# FE.net
KiCad netlist of a schematic drawn in Altium Designer
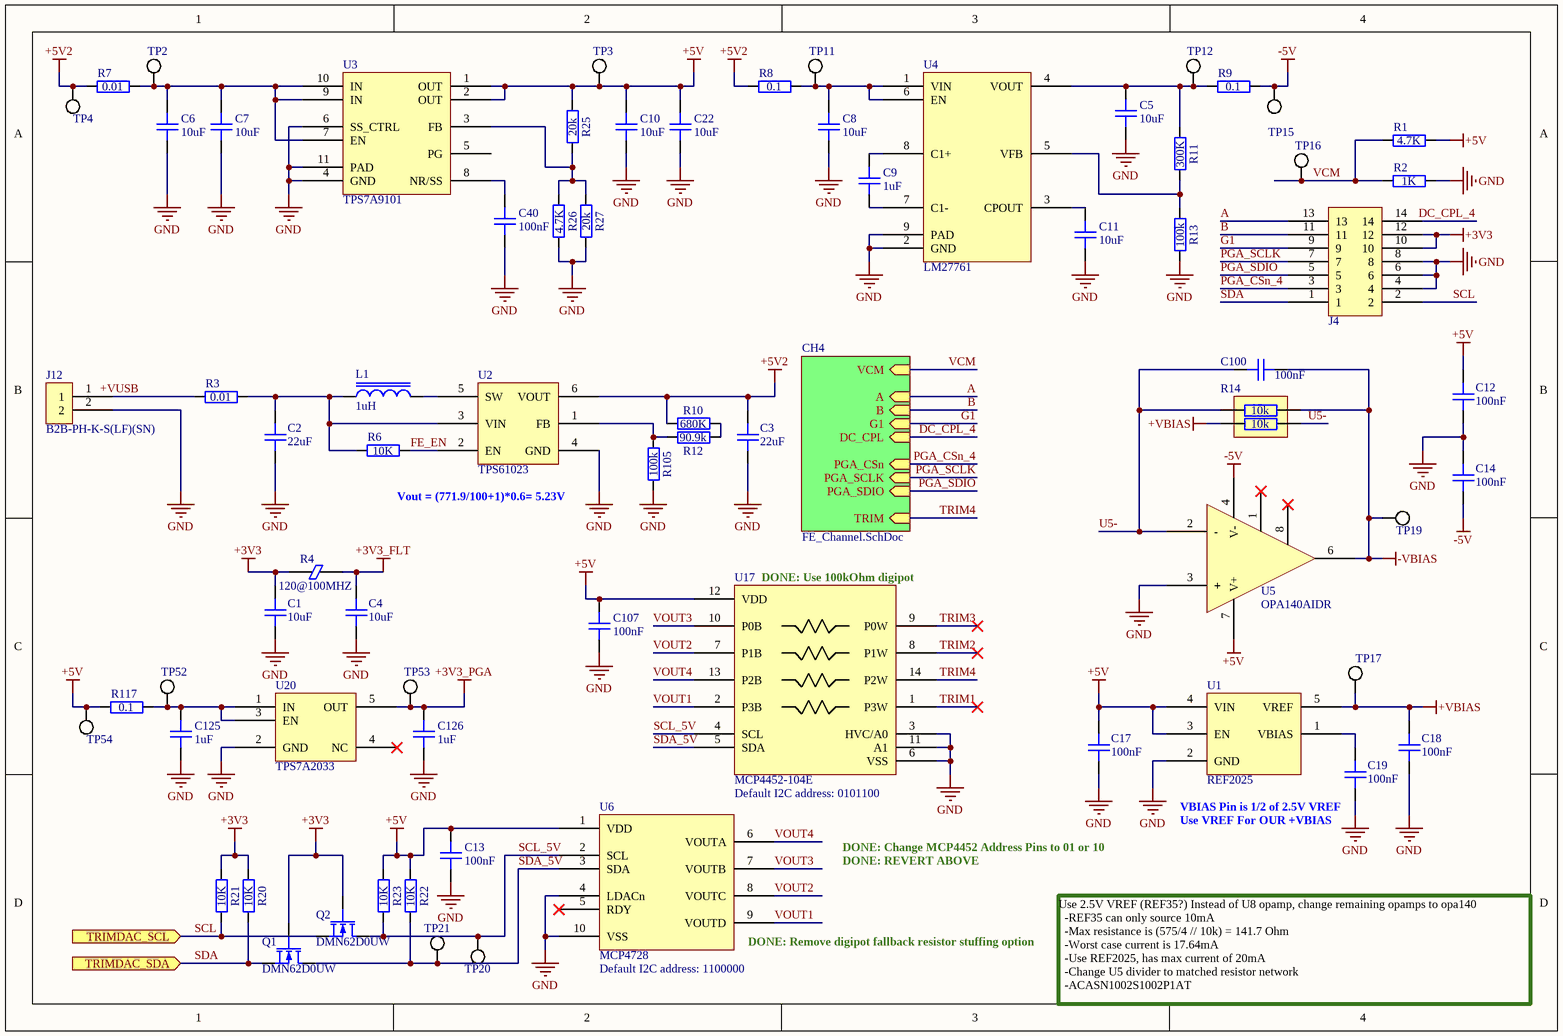
[diagram p0: FE.SchDoc]

(export (version "E")
  (design (tool "Eeschema 10.0.6"))
  (components
    (comp (ref "C1")
      (value "10uF")
      (footprint "GEN_C_0603")
      (fields
        (field (name "MANUFACTURER") "Murata")
        (field (name "HOUSE PART NUMBER") "C-10uF-0603-002")
        (field (name "MANUFACTURER PART NUMBER") "GRM188R61A106ME69D")
      )
      (libsource (lib "DSO") (part "CAP 10uF 10V X5R 0603"))
    )
    (comp (ref "C2")
      (value "22uF")
      (footprint "GEN_C_0805")
      (fields
        (field (name "HOUSE PART NUMBER") "C-22uF-0805-002")
        (field (name "MANUFACTURER") "Murata")
        (field (name "MANUFACTURER PART NUMBER") "GRM21BR61E226ME44L")
      )
      (libsource (lib "DSO") (part "CAP 22uF 25V X5R 0805"))
    )
    (comp (ref "C3")
      (value "22uF")
      (footprint "GEN_C_0805")
      (fields
        (field (name "HOUSE PART NUMBER") "C-22uF-0805-002")
        (field (name "MANUFACTURER") "Murata")
        (field (name "MANUFACTURER PART NUMBER") "GRM21BR61E226ME44L")
      )
      (libsource (lib "DSO") (part "CAP 22uF 25V X5R 0805"))
    )
    (comp (ref "C4")
      (value "10uF")
      (footprint "GEN_C_0603")
      (fields
        (field (name "MANUFACTURER") "Murata")
        (field (name "HOUSE PART NUMBER") "C-10uF-0603-002")
        (field (name "MANUFACTURER PART NUMBER") "GRM188R61A106ME69D")
      )
      (libsource (lib "DSO") (part "CAP 10uF 10V X5R 0603"))
    )
    (comp (ref "C5")
      (value "10uF")
      (footprint "GEN_C_0603")
      (fields
        (field (name "HOUSE PART NUMBER") "C-10uF-0603-002")
        (field (name "MANUFACTURER") "Murata")
        (field (name "MANUFACTURER PART NUMBER") "GRM188R61A106ME69D")
      )
      (libsource (lib "DSO") (part "CAP 10uF 10V X5R 0603"))
    )
    (comp (ref "C6")
      (value "10uF")
      (footprint "GEN_C_0603")
      (fields
        (field (name "HOUSE PART NUMBER") "C-10uF-0603-002")
        (field (name "MANUFACTURER") "Murata")
        (field (name "MANUFACTURER PART NUMBER") "GRM188R61A106ME69D")
      )
      (libsource (lib "DSO") (part "CAP 10uF 10V X5R 0603"))
    )
    (comp (ref "C7")
      (value "10uF")
      (footprint "GEN_C_0603")
      (fields
        (field (name "HOUSE PART NUMBER") "C-10uF-0603-002")
        (field (name "MANUFACTURER") "Murata")
        (field (name "MANUFACTURER PART NUMBER") "GRM188R61A106ME69D")
      )
      (libsource (lib "DSO") (part "CAP 10uF 10V X5R 0603"))
    )
    (comp (ref "C8")
      (value "10uF")
      (footprint "GEN_C_0603")
      (fields
        (field (name "HOUSE PART NUMBER") "C-10uF-0603-002")
        (field (name "MANUFACTURER") "Murata")
        (field (name "MANUFACTURER PART NUMBER") "GRM188R61A106ME69D")
      )
      (libsource (lib "DSO") (part "CAP 10uF 10V X5R 0603"))
    )
    (comp (ref "C9")
      (value "1uF")
      (footprint "GEN_C_0402")
      (fields
        (field (name "MANUFACTURER") "Murata")
        (field (name "MANUFACTURER PART NUMBER") "GRM155R61E105KA12D")
      )
      (libsource (lib "DSO") (part "CAP 1uF 25V X5R 0402"))
    )
    (comp (ref "C10")
      (value "10uF")
      (footprint "GEN_C_0603")
      (fields
        (field (name "HOUSE PART NUMBER") "C-10uF-0603-002")
        (field (name "MANUFACTURER") "Murata")
        (field (name "MANUFACTURER PART NUMBER") "GRM188R61A106ME69D")
      )
      (libsource (lib "DSO") (part "CAP 10uF 10V X5R 0603"))
    )
    (comp (ref "C11")
      (value "10uF")
      (footprint "GEN_C_0603")
      (fields
        (field (name "HOUSE PART NUMBER") "C-10uF-0603-002")
        (field (name "MANUFACTURER") "Murata")
        (field (name "MANUFACTURER PART NUMBER") "GRM188R61A106ME69D")
      )
      (libsource (lib "DSO") (part "CAP 10uF 10V X5R 0603"))
    )
    (comp (ref "C12")
      (value "100nF")
      (footprint "GEN_C_0402")
      (fields
        (field (name "HOUSE PART NUMBER") "C-100nF-0402-002")
        (field (name "MANUFACTURER") "Murata")
        (field (name "MANUFACTURER PART NUMBER") "GCM155R71C104KA55D")
      )
      (libsource (lib "DSO") (part "CAP 100nF 16V X7R 0402"))
    )
    (comp (ref "C13")
      (value "100nF")
      (footprint "GEN_C_0402")
      (fields
        (field (name "HOUSE PART NUMBER") "C-100nF-0402-002")
        (field (name "MANUFACTURER") "Murata")
        (field (name "MANUFACTURER PART NUMBER") "GCM155R71C104KA55D")
      )
      (libsource (lib "DSO") (part "CAP 100nF 16V X7R 0402"))
    )
    (comp (ref "C14")
      (value "100nF")
      (footprint "GEN_C_0402")
      (fields
        (field (name "HOUSE PART NUMBER") "C-100nF-0402-002")
        (field (name "MANUFACTURER") "Murata")
        (field (name "MANUFACTURER PART NUMBER") "GCM155R71C104KA55D")
      )
      (libsource (lib "DSO") (part "CAP 100nF 16V X7R 0402"))
    )
    (comp (ref "C17")
      (value "100nF")
      (footprint "GEN_C_0402")
      (fields
        (field (name "HOUSE PART NUMBER") "C-100nF-0402-002")
        (field (name "MANUFACTURER") "Murata")
        (field (name "MANUFACTURER PART NUMBER") "GCM155R71C104KA55D")
      )
      (libsource (lib "DSO") (part "CAP 100nF 16V X7R 0402"))
    )
    (comp (ref "C18")
      (value "100nF")
      (footprint "GEN_C_0402")
      (fields
        (field (name "HOUSE PART NUMBER") "C-100nF-0402-002")
        (field (name "MANUFACTURER") "Murata")
        (field (name "MANUFACTURER PART NUMBER") "GCM155R71C104KA55D")
      )
      (libsource (lib "DSO") (part "CAP 100nF 16V X7R 0402"))
    )
    (comp (ref "C19")
      (value "100nF")
      (footprint "GEN_C_0402")
      (fields
        (field (name "HOUSE PART NUMBER") "C-100nF-0402-002")
        (field (name "MANUFACTURER") "Murata")
        (field (name "MANUFACTURER PART NUMBER") "GCM155R71C104KA55D")
      )
      (libsource (lib "DSO") (part "CAP 100nF 16V X7R 0402"))
    )
    (comp (ref "C22")
      (value "10uF")
      (footprint "GEN_C_0603")
      (fields
        (field (name "HOUSE PART NUMBER") "C-10uF-0603-002")
        (field (name "MANUFACTURER") "Murata")
        (field (name "MANUFACTURER PART NUMBER") "GRM188R61A106ME69D")
      )
      (libsource (lib "DSO") (part "CAP 10uF 10V X5R 0603"))
    )
    (comp (ref "C40")
      (value "100nF")
      (footprint "GEN_C_0402")
      (fields
        (field (name "MANUFACTURER") "Murata")
        (field (name "HOUSE PART NUMBER") "C-100nF-0402-002")
        (field (name "MANUFACTURER PART NUMBER") "GCM155R71C104KA55D")
      )
      (libsource (lib "DSO") (part "CAP 100nF 16V X7R 0402"))
    )
    (comp (ref "C100")
      (value "100nF")
      (footprint "GEN_C_0402")
      (fields
        (field (name "HOUSE PART NUMBER") "C-100nF-0402-002")
        (field (name "MANUFACTURER") "Murata")
        (field (name "MANUFACTURER PART NUMBER") "GCM155R71C104KA55D")
      )
      (libsource (lib "DSO") (part "CAP 100nF 16V X7R 0402"))
    )
    (comp (ref "C107")
      (value "100nF")
      (footprint "GEN_C_0402")
      (fields
        (field (name "HOUSE PART NUMBER") "C-100nF-0402-002")
        (field (name "MANUFACTURER") "Murata")
        (field (name "MANUFACTURER PART NUMBER") "GCM155R71C104KA55D")
      )
      (libsource (lib "DSO") (part "CAP 100nF 16V X7R 0402"))
    )
    (comp (ref "C125")
      (value "1uF")
      (footprint "GEN_C_0402")
      (fields
        (field (name "MANUFACTURER") "Murata")
        (field (name "MANUFACTURER PART NUMBER") "GRM155R61E105KA12D")
      )
      (libsource (lib "DSO") (part "CAP 1uF 25V X5R 0402"))
    )
    (comp (ref "C126")
      (value "1uF")
      (footprint "GEN_C_0402")
      (fields
        (field (name "MANUFACTURER") "Murata")
        (field (name "MANUFACTURER PART NUMBER") "GRM155R61E105KA12D")
      )
      (libsource (lib "DSO") (part "CAP 1uF 25V X5R 0402"))
    )
    (comp (ref "J4")
      (value "2.54mm 2X7 Pin TH")
      (footprint "GEN_2.54mm_2X7_Pin_TH_RA")
      (libsource (lib "DSO") (part "CONN 2.54mm 2X7 Pin TH RA"))
    )
    (comp (ref "J12")
      (value "B2B-PH-K-S(LF)(SN)")
      (footprint "JST_B2B-PH-K-S(LF)(SN)")
      (fields
        (field (name "MANUFACTURER") "JST")
        (field (name "MANUFACTURER PART NUMBER") "B2B-PH-K-S-LF-SN")
      )
      (libsource (lib "DSO") (part "CONN JST PH 2 Pin TH"))
    )
    (comp (ref "L1")
      (value "1uH")
      (footprint "GEN_L_1210")
      (fields
        (field (name "MANUFACTURER") "Murata")
        (field (name "MANUFACTURER PART NUMBER") "1277AS-H-1R0M=P2")
      )
      (libsource (lib "DSO") (part "IND 1uH 3.1A 45 MOHM 1210"))
    )
    (comp (ref "Q1")
      (value "DMN62D0UW")
      (footprint "GEN_SOT_323")
      (fields (field (name "HOUSE PART NUMBER") "DMN62D0UW-7") (field (name "MANUFACTURER") "Diodes"))
      (libsource (lib "DSO") (part "NMOS DMN62D0UW"))
    )
    (comp (ref "Q2")
      (value "DMN62D0UW")
      (footprint "GEN_SOT_323")
      (fields (field (name "HOUSE PART NUMBER") "DMN62D0UW-7") (field (name "MANUFACTURER") "Diodes"))
      (libsource (lib "DSO") (part "NMOS DMN62D0UW"))
    )
    (comp (ref "R1")
      (value "4.7K")
      (footprint "GEN_R_0402")
      (fields
        (field (name "TOLERANCE") "1%")
        (field (name "MANUFACTURER") "Panasonic")
        (field (name "MANUFACTURER PART NUMBER") "ERJ-2RKF4701X")
      )
      (libsource (lib "DSO") (part "RES 4.7K OHM 1% 1/10W 0402"))
    )
    (comp (ref "R2")
      (value "1K")
      (footprint "GEN_R_0402")
      (fields
        (field (name "TOLERANCE") "1%")
        (field (name "MANUFACTURER") "Yageo")
        (field (name "HOUSE PART NUMBER") "R-1K-0402-1%-001")
      )
      (libsource (lib "DSO") (part "RES 1K OHM 1% 1/10W 0402"))
    )
    (comp (ref "R3")
      (value "0.01")
      (footprint "GEN_R_0603")
      (fields
        (field (name "TOLERANCE") "1%")
        (field (name "HOUSE PART NUMBER") "R-0.01-0603-1%-001")
        (field (name "MANUFACTURER") "Susumu")
      )
      (libsource (lib "") (part "RES 0.01 OHM 1% 1/4W 0603_1"))
    )
    (comp (ref "R4")
      (value "120@100MHZ")
      (footprint "GEN_R_0402")
      (fields (field (name "MANUFACTURER") "Murata") (field (name "HOUSE PART NUMBER") "BLM15PX121SN1D"))
      (libsource (lib "DSO") (part "FERRITE BEAD 120 OHM 0402"))
    )
    (comp (ref "R6")
      (value "10K")
      (footprint "GEN_R_0402")
      (fields
        (field (name "TOLERANCE") "1%")
        (field (name "MANUFACTURER") "Panasonic")
        (field (name "MANUFACTURER PART NUMBER") "ERJ-2RKF1002X")
      )
      (libsource (lib "DSO") (part "RES 10K OHM 1% 1/10W 0402"))
    )
    (comp (ref "R7")
      (value "0.01")
      (footprint "GEN_R_0603")
      (fields
        (field (name "TOLERANCE") "1%")
        (field (name "HOUSE PART NUMBER") "R-0.01-0603-1%-001")
        (field (name "MANUFACTURER") "Susumu")
      )
      (libsource (lib "DSO") (part "RES 0.01 OHM 1% 1/4W 0603"))
    )
    (comp (ref "R8")
      (value "0.1")
      (footprint "GEN_R_0402")
      (fields
        (field (name "TOLERANCE") "1%")
        (field (name "MANUFACTURER") "Panasonic")
        (field (name "MANUFACTURER PART NUMBER") "ERJ-2BSFR10X")
      )
      (libsource (lib "DSO") (part "RES 0.1 OHM 1% 1/6W 0402"))
    )
    (comp (ref "R9")
      (value "0.1")
      (footprint "GEN_R_0402")
      (fields
        (field (name "TOLERANCE") "1%")
        (field (name "MANUFACTURER") "Panasonic")
        (field (name "MANUFACTURER PART NUMBER") "ERJ-2BSFR10X")
      )
      (libsource (lib "DSO") (part "RES 0.1 OHM 1% 1/6W 0402"))
    )
    (comp (ref "R10")
      (value "680K")
      (footprint "GEN_R_0402")
      (fields
        (field (name "TOLERANCE") "1%")
        (field (name "MANUFACTURER") "Yageo")
        (field (name "MANUFACTURER PART NUMBER") "RC0402FR-07681KL")
      )
      (libsource (lib "DSO") (part "RES 680K OHM 1% 1/16W 0402"))
    )
    (comp (ref "R11")
      (value "300K")
      (footprint "GEN_R_0402")
      (fields
        (field (name "TOLERANCE") "1%")
        (field (name "MANUFACTURER") "Panasonic")
        (field (name "MANUFACTURER PART NUMBER") "ERJ-2RKF3003X")
      )
      (libsource (lib "DSO") (part "RES 300K OHM 1% 1/10W 0402"))
    )
    (comp (ref "R12")
      (value "90.9k")
      (footprint "GEN_R_0402")
      (fields
        (field (name "TOLERANCE") "1%")
        (field (name "MANUFACTURER") "Yageo")
        (field (name "MANUFACTURER PART NUMBER") "RC0402FR-0790K9L")
      )
      (libsource (lib "DSO") (part "RES 90.9K OHM 1% 1/16W 0402"))
    )
    (comp (ref "R13")
      (value "100k")
      (footprint "GEN_R_0402")
      (fields
        (field (name "TOLERANCE") "1%")
        (field (name "HOUSE PART NUMBER") "R-100K-0402-1%-001")
        (field (name "MANUFACTURER") "Yageo")
      )
      (libsource (lib "DSO") (part "RES 100K OHM 1% 1/10W 0402"))
    )
    (comp (ref "R14")
      (value "10K")
      (footprint "GEN_R_2ARRAY_0606")
      (fields
        (field (name "TOLERANCE") "1%")
        (field (name "MANUFACTURER") "Vishay Beyschlag")
        (field (name "MANUFACTURER PART NUMBER") "ACASN1002S1002P1ATF1002X")
      )
      (libsource (lib "DSO") (part "RES ARRAY 2x 10K OHM 0.05% 0606"))
    )
    (comp (ref "R20")
      (value "10K")
      (footprint "GEN_R_0402")
      (fields
        (field (name "TOLERANCE") "1%")
        (field (name "MANUFACTURER") "Panasonic")
        (field (name "MANUFACTURER PART NUMBER") "ERJ-2RKF1002X")
      )
      (libsource (lib "") (part "RES 10K OHM 1% 1/10W 0402_1"))
    )
    (comp (ref "R21")
      (value "10K")
      (footprint "GEN_R_0402")
      (fields
        (field (name "TOLERANCE") "1%")
        (field (name "MANUFACTURER") "Panasonic")
        (field (name "MANUFACTURER PART NUMBER") "ERJ-2RKF1002X")
      )
      (libsource (lib "") (part "RES 10K OHM 1% 1/10W 0402_1"))
    )
    (comp (ref "R22")
      (value "10K")
      (footprint "GEN_R_0402")
      (fields
        (field (name "TOLERANCE") "1%")
        (field (name "MANUFACTURER") "Panasonic")
        (field (name "MANUFACTURER PART NUMBER") "ERJ-2RKF1002X")
      )
      (libsource (lib "") (part "RES 10K OHM 1% 1/10W 0402_1"))
    )
    (comp (ref "R23")
      (value "10K")
      (footprint "GEN_R_0402")
      (fields
        (field (name "TOLERANCE") "1%")
        (field (name "MANUFACTURER") "Panasonic")
        (field (name "MANUFACTURER PART NUMBER") "ERJ-2RKF1002X")
      )
      (libsource (lib "") (part "RES 10K OHM 1% 1/10W 0402_1"))
    )
    (comp (ref "R25")
      (value "20k")
      (footprint "GEN_R_0402")
      (fields
        (field (name "TOLERANCE") "1%")
        (field (name "MANUFACTURER") "Yageo")
        (field (name "MANUFACTURER PART NUMBER") "RC0402FR-0720KL")
      )
      (libsource (lib "DSO") (part "RES 20K OHM 1% 1/16W 0402"))
    )
    (comp (ref "R26")
      (value "4.7K")
      (footprint "GEN_R_0402")
      (fields
        (field (name "TOLERANCE") "1%")
        (field (name "MANUFACTURER") "Panasonic")
        (field (name "MANUFACTURER PART NUMBER") "ERJ-2RKF4701X")
      )
      (libsource (lib "DSO") (part "RES 4.7K OHM 1% 1/10W 0402"))
    )
    (comp (ref "R27")
      (value "20k")
      (footprint "GEN_R_0402")
      (fields
        (field (name "TOLERANCE") "1%")
        (field (name "MANUFACTURER") "Yageo")
        (field (name "MANUFACTURER PART NUMBER") "RC0402FR-0720KL")
      )
      (libsource (lib "DSO") (part "RES 20K OHM 1% 1/16W 0402"))
    )
    (comp (ref "R105")
      (value "100k")
      (footprint "GEN_R_0402")
      (fields
        (field (name "TOLERANCE") "1%")
        (field (name "HOUSE PART NUMBER") "R-100K-0402-1%-001")
        (field (name "MANUFACTURER") "Yageo")
      )
      (libsource (lib "DSO") (part "RES 100K OHM 1% 1/10W 0402"))
    )
    (comp (ref "R117")
      (value "0.1")
      (footprint "GEN_R_0402")
      (fields
        (field (name "TOLERANCE") "1%")
        (field (name "MANUFACTURER") "Panasonic")
        (field (name "MANUFACTURER PART NUMBER") "ERJ-2BSFR10X")
      )
      (libsource (lib "DSO") (part "RES 0.1 OHM 1% 1/6W 0402"))
    )
    (comp (ref "TP2") (value "PCB") (footprint "GEN_TP_PCB") (libsource (lib "DSO") (part "TP PCB 1mm")))
    (comp (ref "TP3") (value "PCB") (footprint "GEN_TP_PCB") (libsource (lib "DSO") (part "TP PCB 1mm")))
    (comp (ref "TP4") (value "PCB") (footprint "GEN_TP_PCB") (libsource (lib "DSO") (part "TP PCB 1mm")))
    (comp (ref "TP11") (value "PCB") (footprint "GEN_TP_PCB") (libsource (lib "DSO") (part "TP PCB 1mm")))
    (comp (ref "TP12") (value "PCB") (footprint "GEN_TP_PCB") (libsource (lib "DSO") (part "TP PCB 1mm")))
    (comp (ref "TP15") (value "PCB") (footprint "GEN_TP_PCB") (libsource (lib "DSO") (part "TP PCB 1mm")))
    (comp (ref "TP16") (value "PCB") (footprint "GEN_TP_PCB") (libsource (lib "DSO") (part "TP PCB 1mm")))
    (comp (ref "TP17") (value "PCB") (footprint "GEN_TP_PCB") (libsource (lib "DSO") (part "TP PCB 1mm")))
    (comp (ref "TP19") (value "PCB") (footprint "GEN_TP_PCB") (libsource (lib "DSO") (part "TP PCB 1mm")))
    (comp (ref "TP20") (value "PCB") (footprint "GEN_TP_PCB") (libsource (lib "DSO") (part "TP PCB 1mm")))
    (comp (ref "TP21") (value "PCB") (footprint "GEN_TP_PCB") (libsource (lib "DSO") (part "TP PCB 1mm")))
    (comp (ref "TP52") (value "PCB") (footprint "GEN_TP_PCB") (libsource (lib "DSO") (part "TP PCB 1mm")))
    (comp (ref "TP53") (value "PCB") (footprint "GEN_TP_PCB") (libsource (lib "DSO") (part "TP PCB 1mm")))
    (comp (ref "TP54") (value "PCB") (footprint "GEN_TP_PCB") (libsource (lib "DSO") (part "TP PCB 1mm")))
    (comp (ref "U1")
      (value "REF2025")
      (footprint "GEN_SOT23_5_950_2900X1600X1450")
      (libsource (lib "DSO") (part "IC VREF REF2025"))
    )
    (comp (ref "U2")
      (value "TPS61023")
      (footprint "TI_SOT563_DRL0006A")
      (fields
        (field (name "MANUFACTURER") "Texas Instruments")
        (field (name "MANUFACTURER PART NUMBER") "TPS61023DRLT")
      )
      (libsource (lib "DSO") (part "IC BOOST TPS61023"))
    )
    (comp (ref "U3")
      (value "TPS7A9101")
      (footprint "TI_WSON10_DSK0010A")
      (libsource (lib "DSO") (part "IC LDO TPS7A9101"))
    )
    (comp (ref "U4")
      (value "LM27761")
      (footprint "TI_WSON8_DSG0008A")
      (fields
        (field (name "MANUFACTURER") "Texas Instruments")
        (field (name "MANUFACTURER PART NUMBER") "LM27761DSGR")
      )
      (libsource (lib "DSO") (part "IC CPUMP LM27761"))
    )
    (comp (ref "U5")
      (value "OPA140AIDR")
      (footprint "TI_SOIC8_D0008A")
      (fields (field (name "MANUFACTURER") "Texas Instruments"))
      (libsource (lib "DSO") (part "IC OPAMP OPA140"))
    )
    (comp (ref "U6")
      (value "MCP4728")
      (footprint "MC_MSOP10_UN")
      (fields (field (name "MANUFACTURER") "Microchip"))
      (libsource (lib "DSO") (part "IC DAC QUAD MCP4728"))
    )
    (comp (ref "U17")
      (value "MCP4452-104E")
      (footprint "MC_TSSOP14")
      (fields (field (name "MANUFACTURER") "Microchip"))
      (libsource (lib "DSO") (part "IC DIGIPOT QUAD MCP4452-104E"))
    )
    (comp (ref "U20")
      (value "TPS7A2033")
      (footprint "GEN_SOT23_5_950_2900X1600X1450")
      (fields
        (field (name "MANUFACTURER") "Texas Instruments")
        (field (name "MANUFACTURER PART NUMBER") "TPS7A2033PDBVR")
      )
      (libsource (lib "DSO") (part "IC LDO TPS7A2033"))
    )
  )
  (nets
    (net (code "1") (name "+3V3") (class "Default")
      (node (ref "C1") (pin "2") (pinfunction "2_2") (pintype "passive"))
      (node (ref "J4") (pin "10") (pinfunction "10_10") (pintype "passive"))
      (node (ref "J4") (pin "12") (pinfunction "12_12") (pintype "passive"))
      (node (ref "Q1") (pin "2") (pinfunction "G_2") (pintype "passive"))
      (node (ref "Q2") (pin "2") (pinfunction "G_2") (pintype "passive"))
      (node (ref "R20") (pin "2") (pinfunction "2_2") (pintype "passive"))
      (node (ref "R21") (pin "2") (pinfunction "2_2") (pintype "passive"))
      (node (ref "R4") (pin "1") (pinfunction "1_1") (pintype "passive"))
    )
    (net (code "2") (name "+3V3_FLT") (class "Default")
      (node (ref "C4") (pin "2") (pinfunction "2_2") (pintype "passive"))
      (node (ref "R4") (pin "2") (pinfunction "2_2") (pintype "passive"))
    )
    (net (code "3") (name "+3V3_PGA") (class "Default")
      (node (ref "C126") (pin "2") (pinfunction "2_2") (pintype "passive"))
      (node (ref "TP53") (pin "1") (pinfunction "1_1") (pintype "passive"))
      (node (ref "U20") (pin "5") (pinfunction "OUT_5") (pintype "power_in"))
    )
    (net (code "4") (name "+5V") (class "Default")
      (node (ref "C10") (pin "2") (pinfunction "2_2") (pintype "passive"))
      (node (ref "C107") (pin "2") (pinfunction "2_2") (pintype "passive"))
      (node (ref "C12") (pin "1") (pinfunction "1_1") (pintype "passive"))
      (node (ref "C13") (pin "2") (pinfunction "2_2") (pintype "passive"))
      (node (ref "C17") (pin "1") (pinfunction "1_1") (pintype "passive"))
      (node (ref "C22") (pin "2") (pinfunction "2_2") (pintype "passive"))
      (node (ref "R1") (pin "2") (pinfunction "2_2") (pintype "passive"))
      (node (ref "R117") (pin "1") (pinfunction "1_1") (pintype "passive"))
      (node (ref "R22") (pin "2") (pinfunction "2_2") (pintype "passive"))
      (node (ref "R23") (pin "2") (pinfunction "2_2") (pintype "passive"))
      (node (ref "R25") (pin "2") (pinfunction "2_2") (pintype "passive"))
      (node (ref "TP3") (pin "1") (pinfunction "1_1") (pintype "passive"))
      (node (ref "TP54") (pin "1") (pinfunction "1_1") (pintype "passive"))
      (node (ref "U1") (pin "3") (pinfunction "EN_3") (pintype "passive"))
      (node (ref "U1") (pin "4") (pinfunction "VIN_4") (pintype "passive"))
      (node (ref "U17") (pin "12") (pinfunction "VDD_12") (pintype "power_in"))
      (node (ref "U3") (pin "1") (pinfunction "OUT_1") (pintype "power_in"))
      (node (ref "U3") (pin "2") (pinfunction "OUT_2") (pintype "power_in"))
      (node (ref "U5") (pin "7") (pinfunction "V+_7") (pintype "passive"))
      (node (ref "U6") (pin "1") (pinfunction "VDD_1") (pintype "power_in"))
    )
    (net (code "5") (name "+5V2") (class "Default")
      (node (ref "C3") (pin "2") (pinfunction "2_2") (pintype "passive"))
      (node (ref "R10") (pin "2") (pinfunction "2_2") (pintype "passive"))
      (node (ref "R7") (pin "1") (pinfunction "1_1") (pintype "passive"))
      (node (ref "R8") (pin "1") (pinfunction "1_1") (pintype "passive"))
      (node (ref "TP4") (pin "1") (pinfunction "1_1") (pintype "passive"))
      (node (ref "U2") (pin "6") (pinfunction "VOUT_6") (pintype "passive"))
    )
    (net (code "6") (name "+VBIAS") (class "Default")
      (node (ref "C18") (pin "1") (pinfunction "1_1") (pintype "passive"))
      (node (ref "R14") (pin "2") (pinfunction "2_2") (pintype "passive"))
      (node (ref "TP17") (pin "1") (pinfunction "1_1") (pintype "passive"))
      (node (ref "U1") (pin "5") (pinfunction "VREF_5") (pintype "passive"))
    )
    (net (code "7") (name "-5V") (class "Default")
      (node (ref "C14") (pin "2") (pinfunction "2_2") (pintype "passive"))
      (node (ref "R9") (pin "2") (pinfunction "2_2") (pintype "passive"))
      (node (ref "TP15") (pin "1") (pinfunction "1_1") (pintype "passive"))
      (node (ref "U5") (pin "4") (pinfunction "V-_4") (pintype "passive"))
    )
    (net (code "8") (name "-VBIAS") (class "Default")
      (node (ref "C100") (pin "1") (pinfunction "1_1") (pintype "passive"))
      (node (ref "R14") (pin "4") (pinfunction "4_4") (pintype "passive"))
      (node (ref "TP19") (pin "1") (pinfunction "1_1") (pintype "passive"))
      (node (ref "U5") (pin "6") (pinfunction "OUT_6") (pintype "passive"))
    )
    (net (code "9") (name "/+VUSB") (class "Default")
      (node (ref "J12") (pin "1") (pinfunction "1_1") (pintype "passive"))
      (node (ref "R3") (pin "2") (pinfunction "2_2") (pintype "passive"))
    )
    (net (code "10") (name "/A") (class "Default")
      (node (ref "J4") (pin "13") (pinfunction "13_13") (pintype "passive"))
    )
    (net (code "11") (name "/B") (class "Default")
      (node (ref "J4") (pin "11") (pinfunction "11_11") (pintype "passive"))
    )
    (net (code "12") (name "/DC_CPL_4") (class "Default")
      (node (ref "J4") (pin "14") (pinfunction "14_14") (pintype "passive"))
    )
    (net (code "13") (name "/FE_EN") (class "Default")
      (node (ref "R6") (pin "1") (pinfunction "1_1") (pintype "passive"))
      (node (ref "U2") (pin "2") (pinfunction "EN_2") (pintype "passive"))
    )
    (net (code "14") (name "/G1") (class "Default")
      (node (ref "J4") (pin "9") (pinfunction "9_9") (pintype "passive"))
    )
    (net (code "15") (name "/PGA_CSn_4") (class "Default")
      (node (ref "J4") (pin "3") (pinfunction "3_3") (pintype "passive"))
    )
    (net (code "16") (name "/PGA_SCLK") (class "Default")
      (node (ref "J4") (pin "7") (pinfunction "7_7") (pintype "passive"))
    )
    (net (code "17") (name "/PGA_SDIO") (class "Default")
      (node (ref "J4") (pin "5") (pinfunction "5_5") (pintype "passive"))
    )
    (net (code "18") (name "/SCL") (class "Default")
      (node (ref "J4") (pin "2") (pinfunction "2_2") (pintype "passive"))
      (node (ref "Q2") (pin "3") (pinfunction "S_3") (pintype "passive"))
      (node (ref "R21") (pin "1") (pinfunction "1_1") (pintype "passive"))
    )
    (net (code "19") (name "/SCL_5V") (class "Default")
      (node (ref "Q2") (pin "1") (pinfunction "D_1") (pintype "passive"))
      (node (ref "R23") (pin "1") (pinfunction "1_1") (pintype "passive"))
      (node (ref "TP20") (pin "1") (pinfunction "1_1") (pintype "passive"))
      (node (ref "U17") (pin "4") (pinfunction "SCL_4") (pintype "passive"))
      (node (ref "U6") (pin "2") (pinfunction "SCL_2") (pintype "passive"))
    )
    (net (code "20") (name "/SDA") (class "Default")
      (node (ref "J4") (pin "1") (pinfunction "1_1") (pintype "passive"))
      (node (ref "Q1") (pin "3") (pinfunction "S_3") (pintype "passive"))
      (node (ref "R20") (pin "1") (pinfunction "1_1") (pintype "passive"))
    )
    (net (code "21") (name "/SDA_5V") (class "Default")
      (node (ref "Q1") (pin "1") (pinfunction "D_1") (pintype "passive"))
      (node (ref "R22") (pin "1") (pinfunction "1_1") (pintype "passive"))
      (node (ref "TP21") (pin "1") (pinfunction "1_1") (pintype "passive"))
      (node (ref "U17") (pin "5") (pinfunction "SDA_5") (pintype "passive"))
      (node (ref "U6") (pin "3") (pinfunction "SDA_3") (pintype "passive"))
    )
    (net (code "22") (name "/TRIM1") (class "Default")
      (node (ref "U17") (pin "1") (pinfunction "P3W_1") (pintype "passive+no_connect"))
    )
    (net (code "23") (name "/TRIM2") (class "Default")
      (node (ref "U17") (pin "8") (pinfunction "P1W_8") (pintype "passive+no_connect"))
    )
    (net (code "24") (name "/TRIM3") (class "Default")
      (node (ref "U17") (pin "9") (pinfunction "P0W_9") (pintype "passive+no_connect"))
    )
    (net (code "25") (name "/TRIM4") (class "Default")
      (node (ref "U17") (pin "14") (pinfunction "P2W_14") (pintype "passive"))
    )
    (net (code "26") (name "/U5-") (class "Default")
      (node (ref "C100") (pin "2") (pinfunction "2_2") (pintype "passive"))
      (node (ref "R14") (pin "1") (pinfunction "1_1") (pintype "passive"))
      (node (ref "R14") (pin "3") (pinfunction "3_3") (pintype "passive"))
      (node (ref "U5") (pin "2") (pinfunction "-_2") (pintype "passive"))
    )
    (net (code "27") (name "/VCM") (class "Default")
      (node (ref "R1") (pin "1") (pinfunction "1_1") (pintype "passive"))
      (node (ref "R2") (pin "1") (pinfunction "1_1") (pintype "passive"))
      (node (ref "TP16") (pin "1") (pinfunction "1_1") (pintype "passive"))
    )
    (net (code "28") (name "/VOUT1") (class "Default")
      (node (ref "U17") (pin "2") (pinfunction "P3B_2") (pintype "passive"))
      (node (ref "U6") (pin "9") (pinfunction "VOUTD_9") (pintype "passive"))
    )
    (net (code "29") (name "/VOUT2") (class "Default")
      (node (ref "U17") (pin "7") (pinfunction "P1B_7") (pintype "passive"))
      (node (ref "U6") (pin "8") (pinfunction "VOUTC_8") (pintype "passive"))
    )
    (net (code "30") (name "/VOUT3") (class "Default")
      (node (ref "U17") (pin "10") (pinfunction "P0B_10") (pintype "passive"))
      (node (ref "U6") (pin "7") (pinfunction "VOUTB_7") (pintype "passive"))
    )
    (net (code "31") (name "/VOUT4") (class "Default")
      (node (ref "U17") (pin "13") (pinfunction "P2B_13") (pintype "passive"))
      (node (ref "U6") (pin "6") (pinfunction "VOUTA_6") (pintype "passive"))
    )
    (net (code "32") (name "GND") (class "Default")
      (node (ref "C1") (pin "1") (pinfunction "1_1") (pintype "passive"))
      (node (ref "C10") (pin "1") (pinfunction "1_1") (pintype "passive"))
      (node (ref "C107") (pin "1") (pinfunction "1_1") (pintype "passive"))
      (node (ref "C11") (pin "1") (pinfunction "1_1") (pintype "passive"))
      (node (ref "C12") (pin "2") (pinfunction "2_2") (pintype "passive"))
      (node (ref "C125") (pin "1") (pinfunction "1_1") (pintype "passive"))
      (node (ref "C126") (pin "1") (pinfunction "1_1") (pintype "passive"))
      (node (ref "C13") (pin "1") (pinfunction "1_1") (pintype "passive"))
      (node (ref "C14") (pin "1") (pinfunction "1_1") (pintype "passive"))
      (node (ref "C17") (pin "2") (pinfunction "2_2") (pintype "passive"))
      (node (ref "C18") (pin "2") (pinfunction "2_2") (pintype "passive"))
      (node (ref "C19") (pin "1") (pinfunction "1_1") (pintype "passive"))
      (node (ref "C2") (pin "1") (pinfunction "1_1") (pintype "passive"))
      (node (ref "C22") (pin "1") (pinfunction "1_1") (pintype "passive"))
      (node (ref "C3") (pin "1") (pinfunction "1_1") (pintype "passive"))
      (node (ref "C4") (pin "1") (pinfunction "1_1") (pintype "passive"))
      (node (ref "C40") (pin "1") (pinfunction "1_1") (pintype "passive"))
      (node (ref "C5") (pin "1") (pinfunction "1_1") (pintype "passive"))
      (node (ref "C6") (pin "1") (pinfunction "1_1") (pintype "passive"))
      (node (ref "C7") (pin "1") (pinfunction "1_1") (pintype "passive"))
      (node (ref "C8") (pin "1") (pinfunction "1_1") (pintype "passive"))
      (node (ref "J12") (pin "2") (pinfunction "2_2") (pintype "passive"))
      (node (ref "J4") (pin "4") (pinfunction "4_4") (pintype "passive"))
      (node (ref "J4") (pin "6") (pinfunction "6_6") (pintype "passive"))
      (node (ref "J4") (pin "8") (pinfunction "8_8") (pintype "passive"))
      (node (ref "R105") (pin "1") (pinfunction "1_1") (pintype "passive"))
      (node (ref "R13") (pin "1") (pinfunction "1_1") (pintype "passive"))
      (node (ref "R2") (pin "2") (pinfunction "2_2") (pintype "passive"))
      (node (ref "R26") (pin "1") (pinfunction "1_1") (pintype "passive"))
      (node (ref "R27") (pin "1") (pinfunction "1_1") (pintype "passive"))
      (node (ref "U1") (pin "2") (pinfunction "GND_2") (pintype "passive"))
      (node (ref "U17") (pin "11") (pinfunction "A1_11") (pintype "passive"))
      (node (ref "U17") (pin "3") (pinfunction "HVC/A0_3") (pintype "passive"))
      (node (ref "U17") (pin "6") (pinfunction "VSS_6") (pintype "power_in"))
      (node (ref "U2") (pin "4") (pinfunction "GND_4") (pintype "power_in"))
      (node (ref "U20") (pin "2") (pinfunction "GND_2") (pintype "power_in"))
      (node (ref "U3") (pin "11") (pinfunction "PAD_11") (pintype "passive"))
      (node (ref "U3") (pin "4") (pinfunction "GND_4") (pintype "power_in"))
      (node (ref "U3") (pin "6") (pinfunction "SS_CTRL_6") (pintype "passive"))
      (node (ref "U4") (pin "2") (pinfunction "GND_2") (pintype "power_in"))
      (node (ref "U4") (pin "9") (pinfunction "PAD_9") (pintype "power_in"))
      (node (ref "U5") (pin "3") (pinfunction "+_3") (pintype "passive"))
      (node (ref "U6") (pin "10") (pinfunction "VSS_10") (pintype "power_in"))
      (node (ref "U6") (pin "4") (pinfunction "LDACn_4") (pintype "passive"))
    )
    (net (code "33") (name "Net-(R10-Pad1)") (class "Default")
      (node (ref "R10") (pin "1") (pinfunction "1_1") (pintype "passive"))
      (node (ref "R12") (pin "2") (pinfunction "2_2") (pintype "passive"))
    )
    (net (code "34") (name "Net-(U1-VBIAS)") (class "Default")
      (node (ref "C19") (pin "2") (pinfunction "2_2") (pintype "passive"))
      (node (ref "U1") (pin "1") (pinfunction "VBIAS_1") (pintype "power_in"))
    )
    (net (code "35") (name "Net-(U2-FB)") (class "Default")
      (node (ref "R105") (pin "2") (pinfunction "2_2") (pintype "passive"))
      (node (ref "R12") (pin "1") (pinfunction "1_1") (pintype "passive"))
      (node (ref "U2") (pin "1") (pinfunction "FB_1") (pintype "passive"))
    )
    (net (code "36") (name "Net-(U2-SW)") (class "Default")
      (node (ref "L1") (pin "2") (pinfunction "2_2") (pintype "passive"))
      (node (ref "U2") (pin "5") (pinfunction "SW_5") (pintype "passive"))
    )
    (net (code "37") (name "Net-(U2-VIN)") (class "Default")
      (node (ref "C2") (pin "2") (pinfunction "2_2") (pintype "passive"))
      (node (ref "L1") (pin "1") (pinfunction "1_1") (pintype "passive"))
      (node (ref "R3") (pin "1") (pinfunction "1_1") (pintype "passive"))
      (node (ref "R6") (pin "2") (pinfunction "2_2") (pintype "passive"))
      (node (ref "U2") (pin "3") (pinfunction "VIN_3") (pintype "power_in"))
    )
    (net (code "38") (name "Net-(U3-EN)") (class "Default")
      (node (ref "C6") (pin "2") (pinfunction "2_2") (pintype "passive"))
      (node (ref "C7") (pin "2") (pinfunction "2_2") (pintype "passive"))
      (node (ref "R7") (pin "2") (pinfunction "2_2") (pintype "passive"))
      (node (ref "TP2") (pin "1") (pinfunction "1_1") (pintype "passive"))
      (node (ref "U3") (pin "10") (pinfunction "IN_10") (pintype "power_in"))
      (node (ref "U3") (pin "7") (pinfunction "EN_7") (pintype "passive"))
      (node (ref "U3") (pin "9") (pinfunction "IN_9") (pintype "power_in"))
    )
    (net (code "39") (name "Net-(U3-FB)") (class "Default")
      (node (ref "R25") (pin "1") (pinfunction "1_1") (pintype "passive"))
      (node (ref "R26") (pin "2") (pinfunction "2_2") (pintype "passive"))
      (node (ref "R27") (pin "2") (pinfunction "2_2") (pintype "passive"))
      (node (ref "U3") (pin "3") (pinfunction "FB_3") (pintype "passive"))
    )
    (net (code "40") (name "Net-(U3-NR{slash}SS)") (class "Default")
      (node (ref "C40") (pin "2") (pinfunction "2_2") (pintype "passive"))
      (node (ref "U3") (pin "8") (pinfunction "NR/SS_8") (pintype "passive"))
    )
    (net (code "41") (name "Net-(U4-C1+)") (class "Default")
      (node (ref "C9") (pin "2") (pinfunction "2_2") (pintype "passive"))
      (node (ref "U4") (pin "8") (pinfunction "C1+_8") (pintype "passive"))
    )
    (net (code "42") (name "Net-(U4-C1-)") (class "Default")
      (node (ref "C9") (pin "1") (pinfunction "1_1") (pintype "passive"))
      (node (ref "U4") (pin "7") (pinfunction "C1-_7") (pintype "passive"))
    )
    (net (code "43") (name "Net-(U4-CPOUT)") (class "Default")
      (node (ref "C11") (pin "2") (pinfunction "2_2") (pintype "passive"))
      (node (ref "U4") (pin "3") (pinfunction "CPOUT_3") (pintype "passive"))
    )
    (net (code "44") (name "Net-(U4-EN)") (class "Default")
      (node (ref "C8") (pin "2") (pinfunction "2_2") (pintype "passive"))
      (node (ref "R8") (pin "2") (pinfunction "2_2") (pintype "passive"))
      (node (ref "TP11") (pin "1") (pinfunction "1_1") (pintype "passive"))
      (node (ref "U4") (pin "1") (pinfunction "VIN_1") (pintype "power_in"))
      (node (ref "U4") (pin "6") (pinfunction "EN_6") (pintype "passive"))
    )
    (net (code "45") (name "Net-(U4-VFB)") (class "Default")
      (node (ref "R11") (pin "1") (pinfunction "1_1") (pintype "passive"))
      (node (ref "R13") (pin "2") (pinfunction "2_2") (pintype "passive"))
      (node (ref "U4") (pin "5") (pinfunction "VFB_5") (pintype "passive"))
    )
    (net (code "46") (name "Net-(U4-VOUT)") (class "Default")
      (node (ref "C5") (pin "2") (pinfunction "2_2") (pintype "passive"))
      (node (ref "R11") (pin "2") (pinfunction "2_2") (pintype "passive"))
      (node (ref "R9") (pin "1") (pinfunction "1_1") (pintype "passive"))
      (node (ref "TP12") (pin "1") (pinfunction "1_1") (pintype "passive"))
      (node (ref "U4") (pin "4") (pinfunction "VOUT_4") (pintype "power_in"))
    )
    (net (code "47") (name "Net-(U20-EN)") (class "Default")
      (node (ref "C125") (pin "2") (pinfunction "2_2") (pintype "passive"))
      (node (ref "R117") (pin "2") (pinfunction "2_2") (pintype "passive"))
      (node (ref "TP52") (pin "1") (pinfunction "1_1") (pintype "passive"))
      (node (ref "U20") (pin "1") (pinfunction "IN_1") (pintype "power_in"))
      (node (ref "U20") (pin "3") (pinfunction "EN_3") (pintype "passive"))
    )
    (net (code "48") (name "unconnected-(U3-PG-Pad5)") (class "Default")
      (node (ref "U3") (pin "5") (pinfunction "PG_5") (pintype "passive"))
    )
    (net (code "49") (name "unconnected-(U5-N1-Pad1)") (class "Default")
      (node (ref "U5") (pin "1") (pinfunction "N1_1") (pintype "passive+no_connect"))
    )
    (net (code "50") (name "unconnected-(U5-N2-Pad8)") (class "Default")
      (node (ref "U5") (pin "8") (pinfunction "N2_8") (pintype "passive+no_connect"))
    )
    (net (code "51") (name "unconnected-(U6-RDY-Pad5)") (class "Default")
      (node (ref "U6") (pin "5") (pinfunction "RDY_5") (pintype "passive+no_connect"))
    )
    (net (code "52") (name "unconnected-(U20-NC-Pad4)") (class "Default")
      (node (ref "U20") (pin "4") (pinfunction "NC_4") (pintype "passive+no_connect"))
    )
  )
)
